# main.net
KiCad netlist of a schematic drawn in Altium Designer
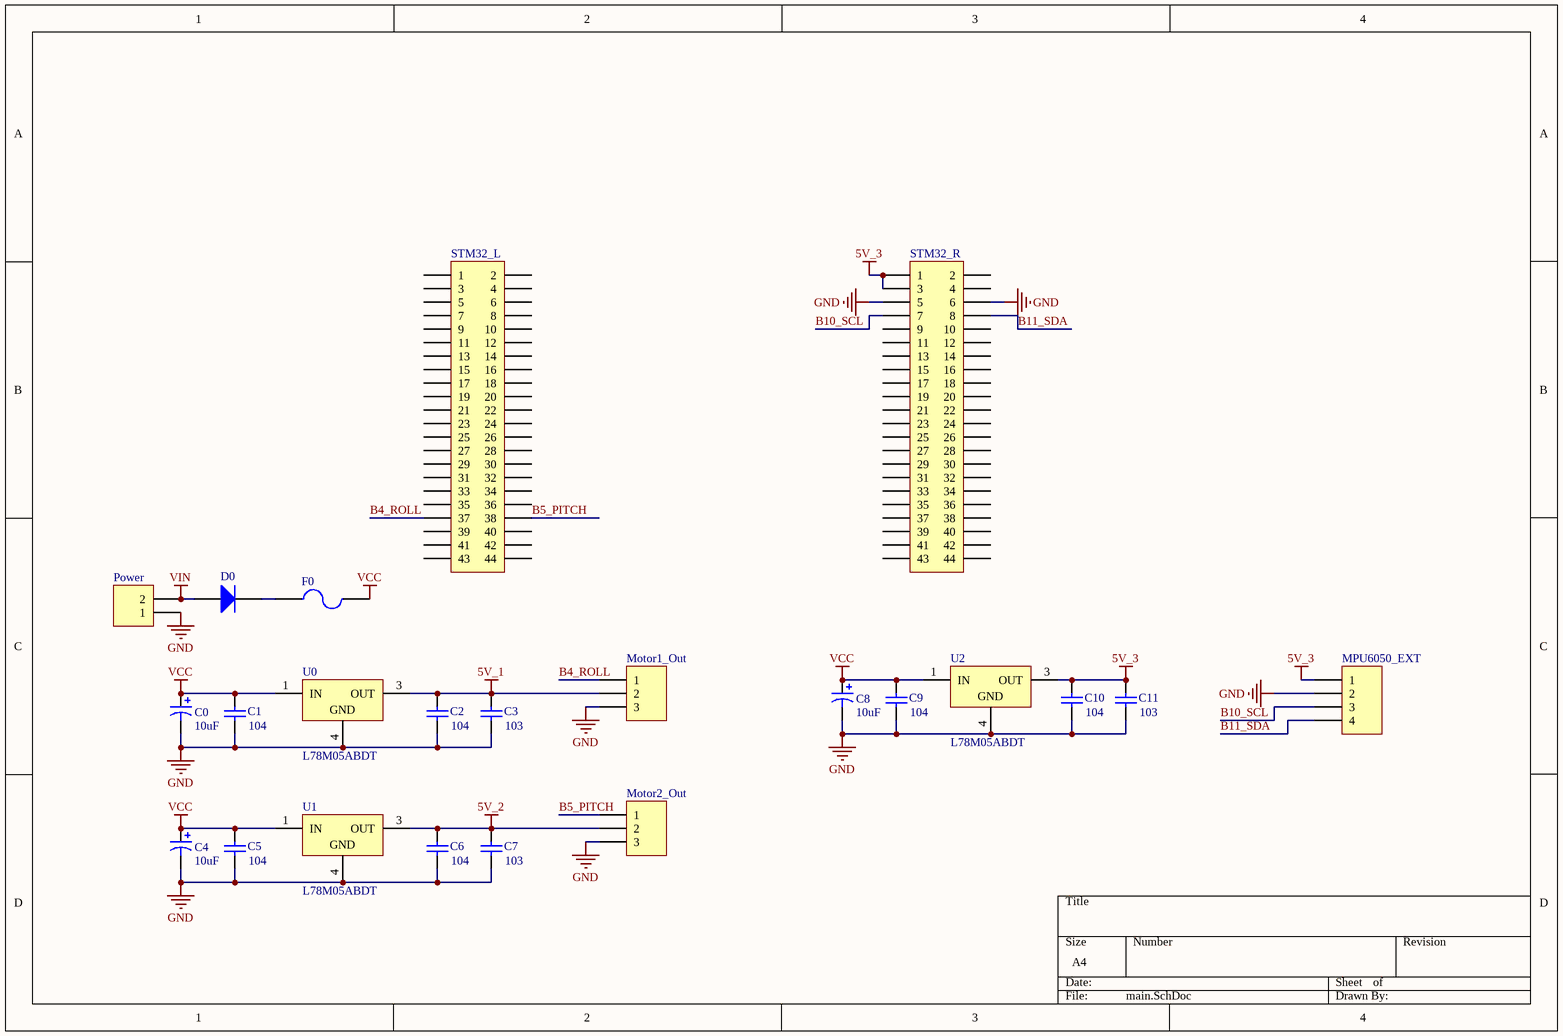
[diagram p0: main.SchDoc]

(export (version "E")
  (design (tool "Eeschema 10.0.6"))
  (components
    (comp (ref "C0")
      (value "10uF")
      (footprint "元件库:1206A")
      (description "Polarized Capacitor (Radial)")
      (fields (field (name "Comment") "Cap Pol1") (field (name "PUBLISHER") "Altium Limited"))
      (libsource (lib "Miscellaneous Devices") (part "Cap Pol1"))
    )
    (comp (ref "C1")
      (value "104")
      (footprint "STM32waiweilingjian:0805")
      (description "Capacitor (Semiconductor SIM Model)")
      (fields (field (name "Comment") "Cap Semi") (field (name "PUBLISHER") "Altium Limited"))
      (libsource (lib "Miscellaneous Devices") (part "Cap Semi"))
    )
    (comp (ref "C2")
      (value "104")
      (footprint "STM32waiweilingjian:0805")
      (description "Capacitor (Semiconductor SIM Model)")
      (fields (field (name "Comment") "Cap Semi") (field (name "PUBLISHER") "Altium Limited"))
      (libsource (lib "Miscellaneous Devices") (part "Cap Semi"))
    )
    (comp (ref "C3")
      (value "103")
      (footprint "STM32waiweilingjian:0805")
      (description "Capacitor (Semiconductor SIM Model)")
      (fields (field (name "Comment") "Cap Semi") (field (name "PUBLISHER") "Altium Limited"))
      (libsource (lib "Miscellaneous Devices") (part "Cap Semi"))
    )
    (comp (ref "C4")
      (value "10uF")
      (footprint "元件库:1206A")
      (description "Polarized Capacitor (Radial)")
      (fields (field (name "Comment") "Cap Pol1") (field (name "PUBLISHER") "Altium Limited"))
      (libsource (lib "Miscellaneous Devices") (part "Cap Pol1"))
    )
    (comp (ref "C5")
      (value "104")
      (footprint "STM32waiweilingjian:0805")
      (description "Capacitor (Semiconductor SIM Model)")
      (fields (field (name "Comment") "Cap Semi") (field (name "PUBLISHER") "Altium Limited"))
      (libsource (lib "Miscellaneous Devices") (part "Cap Semi"))
    )
    (comp (ref "C6")
      (value "104")
      (footprint "STM32waiweilingjian:0805")
      (description "Capacitor (Semiconductor SIM Model)")
      (fields (field (name "Comment") "Cap Semi") (field (name "PUBLISHER") "Altium Limited"))
      (libsource (lib "Miscellaneous Devices") (part "Cap Semi"))
    )
    (comp (ref "C7")
      (value "103")
      (footprint "STM32waiweilingjian:0805")
      (description "Capacitor (Semiconductor SIM Model)")
      (fields (field (name "Comment") "Cap Semi") (field (name "PUBLISHER") "Altium Limited"))
      (libsource (lib "Miscellaneous Devices") (part "Cap Semi"))
    )
    (comp (ref "C8")
      (value "10uF")
      (footprint "元件库:1206A")
      (description "Polarized Capacitor (Radial)")
      (fields (field (name "Comment") "Cap Pol1") (field (name "PUBLISHER") "Altium Limited"))
      (libsource (lib "Miscellaneous Devices") (part "Cap Pol1"))
    )
    (comp (ref "C9")
      (value "104")
      (footprint "STM32waiweilingjian:0805")
      (description "Capacitor (Semiconductor SIM Model)")
      (fields (field (name "Comment") "Cap Semi") (field (name "PUBLISHER") "Altium Limited"))
      (libsource (lib "Miscellaneous Devices") (part "Cap Semi"))
    )
    (comp (ref "C10")
      (value "104")
      (footprint "STM32waiweilingjian:0805")
      (description "Capacitor (Semiconductor SIM Model)")
      (fields (field (name "Comment") "Cap Semi") (field (name "PUBLISHER") "Altium Limited"))
      (libsource (lib "Miscellaneous Devices") (part "Cap Semi"))
    )
    (comp (ref "C11")
      (value "103")
      (footprint "STM32waiweilingjian:0805")
      (description "Capacitor (Semiconductor SIM Model)")
      (fields (field (name "Comment") "Cap Semi") (field (name "PUBLISHER") "Altium Limited"))
      (libsource (lib "Miscellaneous Devices") (part "Cap Semi"))
    )
    (comp (ref "D0")
      (value "Diode")
      (footprint "fszhang:DIODE-1206")
      (description "Default Diode")
      (fields (field (name "PUBLISHER") "Altium Limited"))
      (libsource (lib "Miscellaneous Devices") (part "Diode"))
    )
    (comp (ref "F0")
      (value "Fuse 2")
      (footprint "Miscellaneous Devices:1812")
      (description "Fuse")
      (fields (field (name "PUBLISHER") "Altium Limited"))
      (libsource (lib "Miscellaneous Devices") (part "Fuse 2"))
    )
    (comp (ref "Motor1_Out")
      (value "Header 3")
      (footprint "HDR1X3")
      (description "Header, 3-Pin")
      (fields (field (name "PUBLISHER") "Altium Limited"))
      (libsource (lib "Miscellaneous Connectors") (part "Header 3"))
    )
    (comp (ref "Motor2_Out")
      (value "Header 3")
      (footprint "HDR1X3")
      (description "Header, 3-Pin")
      (fields (field (name "PUBLISHER") "Altium Limited"))
      (libsource (lib "Miscellaneous Connectors") (part "Header 3"))
    )
    (comp (ref "MPU6050_EXT")
      (value "Header 4")
      (footprint "HDR1X4")
      (description "Header, 4-Pin")
      (fields (field (name "PUBLISHER") "Altium Limited"))
      (libsource (lib "Miscellaneous Connectors") (part "Header 4"))
    )
    (comp (ref "Power")
      (value "Header 2")
      (footprint "HDR1X2")
      (description "Header, 2-Pin")
      (fields (field (name "PUBLISHER") "Altium Limited"))
      (libsource (lib "Miscellaneous Connectors") (part "Header 2"))
    )
    (comp (ref "STM32_L")
      (value "Header 22X2")
      (footprint "HDR2X22")
      (description "Header, 22-Pin, Dual row")
      (fields (field (name "PUBLISHER") "Altium Limited"))
      (libsource (lib "Miscellaneous Connectors") (part "Header 22X2"))
    )
    (comp (ref "STM32_R")
      (value "Header 22X2")
      (footprint "HDR2X22")
      (description "Header, 22-Pin, Dual row")
      (fields (field (name "PUBLISHER") "Altium Limited"))
      (libsource (lib "Miscellaneous Connectors") (part "Header 22X2"))
    )
    (comp (ref "U0")
      (value "L78M05ABDT")
      (footprint "TO-252")
      (description "Precision 500mA Regulator")
      (fields (field (name "PUBLISHER") "Altium Limited"))
      (libsource (lib "ST Power Mgt Voltage Regulator") (part "L78M05ABDT"))
    )
    (comp (ref "U1")
      (value "L78M05ABDT")
      (footprint "TO-252")
      (description "Precision 500mA Regulator")
      (fields (field (name "PUBLISHER") "Altium Limited"))
      (libsource (lib "ST Power Mgt Voltage Regulator") (part "L78M05ABDT"))
    )
    (comp (ref "U2")
      (value "L78M05ABDT")
      (footprint "TO-252")
      (description "Precision 500mA Regulator")
      (fields (field (name "PUBLISHER") "Altium Limited"))
      (libsource (lib "ST Power Mgt Voltage Regulator") (part "L78M05ABDT"))
    )
  )
  (nets
    (net (code "1") (name "/B4_ROLL") (class "Default")
      (node (ref "Motor1_Out") (pin "1") (pinfunction "1_1") (pintype "passive"))
      (node (ref "STM32_L") (pin "37") (pinfunction "37_37") (pintype "passive"))
    )
    (net (code "2") (name "/B5_PITCH") (class "Default")
      (node (ref "Motor2_Out") (pin "1") (pinfunction "1_1") (pintype "passive"))
      (node (ref "STM32_L") (pin "38") (pinfunction "38_38") (pintype "passive"))
    )
    (net (code "3") (name "/B10_SCL") (class "Default")
      (node (ref "MPU6050_EXT") (pin "3") (pinfunction "3_3") (pintype "passive"))
      (node (ref "STM32_R") (pin "7") (pinfunction "7_7") (pintype "passive"))
    )
    (net (code "4") (name "/B11_SDA") (class "Default")
      (node (ref "MPU6050_EXT") (pin "4") (pinfunction "4_4") (pintype "passive"))
      (node (ref "STM32_R") (pin "8") (pinfunction "8_8") (pintype "passive"))
    )
    (net (code "5") (name "5V_1") (class "Default")
      (node (ref "C2") (pin "2") (pinfunction "2_2") (pintype "passive"))
      (node (ref "C3") (pin "2") (pinfunction "2_2") (pintype "passive"))
      (node (ref "Motor1_Out") (pin "2") (pinfunction "2_2") (pintype "passive"))
      (node (ref "U0") (pin "3") (pinfunction "OUT_3") (pintype "power_in"))
    )
    (net (code "6") (name "5V_2") (class "Default")
      (node (ref "C6") (pin "2") (pinfunction "2_2") (pintype "passive"))
      (node (ref "C7") (pin "2") (pinfunction "2_2") (pintype "passive"))
      (node (ref "Motor2_Out") (pin "2") (pinfunction "2_2") (pintype "passive"))
      (node (ref "U1") (pin "3") (pinfunction "OUT_3") (pintype "power_in"))
    )
    (net (code "7") (name "5V_3") (class "Default")
      (node (ref "C10") (pin "2") (pinfunction "2_2") (pintype "passive"))
      (node (ref "C11") (pin "2") (pinfunction "2_2") (pintype "passive"))
      (node (ref "MPU6050_EXT") (pin "1") (pinfunction "1_1") (pintype "passive"))
      (node (ref "STM32_R") (pin "1") (pinfunction "1_1") (pintype "passive"))
      (node (ref "STM32_R") (pin "3") (pinfunction "3_3") (pintype "passive"))
      (node (ref "U2") (pin "3") (pinfunction "OUT_3") (pintype "power_in"))
    )
    (net (code "8") (name "GND") (class "Default")
      (node (ref "C0") (pin "2") (pinfunction "2_2") (pintype "passive"))
      (node (ref "C1") (pin "1") (pinfunction "1_1") (pintype "passive"))
      (node (ref "C10") (pin "1") (pinfunction "1_1") (pintype "passive"))
      (node (ref "C11") (pin "1") (pinfunction "1_1") (pintype "passive"))
      (node (ref "C2") (pin "1") (pinfunction "1_1") (pintype "passive"))
      (node (ref "C3") (pin "1") (pinfunction "1_1") (pintype "passive"))
      (node (ref "C4") (pin "2") (pinfunction "2_2") (pintype "passive"))
      (node (ref "C5") (pin "1") (pinfunction "1_1") (pintype "passive"))
      (node (ref "C6") (pin "1") (pinfunction "1_1") (pintype "passive"))
      (node (ref "C7") (pin "1") (pinfunction "1_1") (pintype "passive"))
      (node (ref "C8") (pin "2") (pinfunction "2_2") (pintype "passive"))
      (node (ref "C9") (pin "1") (pinfunction "1_1") (pintype "passive"))
      (node (ref "MPU6050_EXT") (pin "2") (pinfunction "2_2") (pintype "passive"))
      (node (ref "Motor1_Out") (pin "3") (pinfunction "3_3") (pintype "passive"))
      (node (ref "Motor2_Out") (pin "3") (pinfunction "3_3") (pintype "passive"))
      (node (ref "Power") (pin "1") (pinfunction "1_1") (pintype "passive"))
      (node (ref "STM32_R") (pin "5") (pinfunction "5_5") (pintype "passive"))
      (node (ref "STM32_R") (pin "6") (pinfunction "6_6") (pintype "passive"))
      (node (ref "U0") (pin "4") (pinfunction "GND_4") (pintype "power_in"))
      (node (ref "U1") (pin "4") (pinfunction "GND_4") (pintype "power_in"))
      (node (ref "U2") (pin "4") (pinfunction "GND_4") (pintype "power_in"))
    )
    (net (code "9") (name "Net-(D0-K)") (class "Default")
      (node (ref "D0") (pin "2") (pinfunction "K_2") (pintype "passive"))
      (node (ref "F0") (pin "1") (pinfunction "1_1") (pintype "passive"))
    )
    (net (code "10") (name "VCC") (class "Default")
      (node (ref "C0") (pin "1") (pinfunction "1_1") (pintype "passive"))
      (node (ref "C1") (pin "2") (pinfunction "2_2") (pintype "passive"))
      (node (ref "C4") (pin "1") (pinfunction "1_1") (pintype "passive"))
      (node (ref "C5") (pin "2") (pinfunction "2_2") (pintype "passive"))
      (node (ref "C8") (pin "1") (pinfunction "1_1") (pintype "passive"))
      (node (ref "C9") (pin "2") (pinfunction "2_2") (pintype "passive"))
      (node (ref "F0") (pin "2") (pinfunction "2_2") (pintype "passive"))
      (node (ref "U0") (pin "1") (pinfunction "IN_1") (pintype "power_in"))
      (node (ref "U1") (pin "1") (pinfunction "IN_1") (pintype "power_in"))
      (node (ref "U2") (pin "1") (pinfunction "IN_1") (pintype "power_in"))
    )
    (net (code "11") (name "VIN") (class "Default")
      (node (ref "D0") (pin "1") (pinfunction "A_1") (pintype "passive"))
      (node (ref "Power") (pin "2") (pinfunction "2_2") (pintype "passive"))
    )
    (net (code "12") (name "unconnected-(STM32_L-Pad1)") (class "Default")
      (node (ref "STM32_L") (pin "1") (pinfunction "1_1") (pintype "passive"))
    )
    (net (code "13") (name "unconnected-(STM32_L-Pad2)") (class "Default")
      (node (ref "STM32_L") (pin "2") (pinfunction "2_2") (pintype "passive"))
    )
    (net (code "14") (name "unconnected-(STM32_L-Pad3)") (class "Default")
      (node (ref "STM32_L") (pin "3") (pinfunction "3_3") (pintype "passive"))
    )
    (net (code "15") (name "unconnected-(STM32_L-Pad4)") (class "Default")
      (node (ref "STM32_L") (pin "4") (pinfunction "4_4") (pintype "passive"))
    )
    (net (code "16") (name "unconnected-(STM32_L-Pad5)") (class "Default")
      (node (ref "STM32_L") (pin "5") (pinfunction "5_5") (pintype "passive"))
    )
    (net (code "17") (name "unconnected-(STM32_L-Pad6)") (class "Default")
      (node (ref "STM32_L") (pin "6") (pinfunction "6_6") (pintype "passive"))
    )
    (net (code "18") (name "unconnected-(STM32_L-Pad7)") (class "Default")
      (node (ref "STM32_L") (pin "7") (pinfunction "7_7") (pintype "passive"))
    )
    (net (code "19") (name "unconnected-(STM32_L-Pad8)") (class "Default")
      (node (ref "STM32_L") (pin "8") (pinfunction "8_8") (pintype "passive"))
    )
    (net (code "20") (name "unconnected-(STM32_L-Pad9)") (class "Default")
      (node (ref "STM32_L") (pin "9") (pinfunction "9_9") (pintype "passive"))
    )
    (net (code "21") (name "unconnected-(STM32_L-Pad10)") (class "Default")
      (node (ref "STM32_L") (pin "10") (pinfunction "10_10") (pintype "passive"))
    )
    (net (code "22") (name "unconnected-(STM32_L-Pad11)") (class "Default")
      (node (ref "STM32_L") (pin "11") (pinfunction "11_11") (pintype "passive"))
    )
    (net (code "23") (name "unconnected-(STM32_L-Pad12)") (class "Default")
      (node (ref "STM32_L") (pin "12") (pinfunction "12_12") (pintype "passive"))
    )
    (net (code "24") (name "unconnected-(STM32_L-Pad13)") (class "Default")
      (node (ref "STM32_L") (pin "13") (pinfunction "13_13") (pintype "passive"))
    )
    (net (code "25") (name "unconnected-(STM32_L-Pad14)") (class "Default")
      (node (ref "STM32_L") (pin "14") (pinfunction "14_14") (pintype "passive"))
    )
    (net (code "26") (name "unconnected-(STM32_L-Pad15)") (class "Default")
      (node (ref "STM32_L") (pin "15") (pinfunction "15_15") (pintype "passive"))
    )
    (net (code "27") (name "unconnected-(STM32_L-Pad16)") (class "Default")
      (node (ref "STM32_L") (pin "16") (pinfunction "16_16") (pintype "passive"))
    )
    (net (code "28") (name "unconnected-(STM32_L-Pad17)") (class "Default")
      (node (ref "STM32_L") (pin "17") (pinfunction "17_17") (pintype "passive"))
    )
    (net (code "29") (name "unconnected-(STM32_L-Pad18)") (class "Default")
      (node (ref "STM32_L") (pin "18") (pinfunction "18_18") (pintype "passive"))
    )
    (net (code "30") (name "unconnected-(STM32_L-Pad19)") (class "Default")
      (node (ref "STM32_L") (pin "19") (pinfunction "19_19") (pintype "passive"))
    )
    (net (code "31") (name "unconnected-(STM32_L-Pad20)") (class "Default")
      (node (ref "STM32_L") (pin "20") (pinfunction "20_20") (pintype "passive"))
    )
    (net (code "32") (name "unconnected-(STM32_L-Pad21)") (class "Default")
      (node (ref "STM32_L") (pin "21") (pinfunction "21_21") (pintype "passive"))
    )
    (net (code "33") (name "unconnected-(STM32_L-Pad22)") (class "Default")
      (node (ref "STM32_L") (pin "22") (pinfunction "22_22") (pintype "passive"))
    )
    (net (code "34") (name "unconnected-(STM32_L-Pad23)") (class "Default")
      (node (ref "STM32_L") (pin "23") (pinfunction "23_23") (pintype "passive"))
    )
    (net (code "35") (name "unconnected-(STM32_L-Pad24)") (class "Default")
      (node (ref "STM32_L") (pin "24") (pinfunction "24_24") (pintype "passive"))
    )
    (net (code "36") (name "unconnected-(STM32_L-Pad25)") (class "Default")
      (node (ref "STM32_L") (pin "25") (pinfunction "25_25") (pintype "passive"))
    )
    (net (code "37") (name "unconnected-(STM32_L-Pad26)") (class "Default")
      (node (ref "STM32_L") (pin "26") (pinfunction "26_26") (pintype "passive"))
    )
    (net (code "38") (name "unconnected-(STM32_L-Pad27)") (class "Default")
      (node (ref "STM32_L") (pin "27") (pinfunction "27_27") (pintype "passive"))
    )
    (net (code "39") (name "unconnected-(STM32_L-Pad28)") (class "Default")
      (node (ref "STM32_L") (pin "28") (pinfunction "28_28") (pintype "passive"))
    )
    (net (code "40") (name "unconnected-(STM32_L-Pad29)") (class "Default")
      (node (ref "STM32_L") (pin "29") (pinfunction "29_29") (pintype "passive"))
    )
    (net (code "41") (name "unconnected-(STM32_L-Pad30)") (class "Default")
      (node (ref "STM32_L") (pin "30") (pinfunction "30_30") (pintype "passive"))
    )
    (net (code "42") (name "unconnected-(STM32_L-Pad31)") (class "Default")
      (node (ref "STM32_L") (pin "31") (pinfunction "31_31") (pintype "passive"))
    )
    (net (code "43") (name "unconnected-(STM32_L-Pad32)") (class "Default")
      (node (ref "STM32_L") (pin "32") (pinfunction "32_32") (pintype "passive"))
    )
    (net (code "44") (name "unconnected-(STM32_L-Pad33)") (class "Default")
      (node (ref "STM32_L") (pin "33") (pinfunction "33_33") (pintype "passive"))
    )
    (net (code "45") (name "unconnected-(STM32_L-Pad34)") (class "Default")
      (node (ref "STM32_L") (pin "34") (pinfunction "34_34") (pintype "passive"))
    )
    (net (code "46") (name "unconnected-(STM32_L-Pad35)") (class "Default")
      (node (ref "STM32_L") (pin "35") (pinfunction "35_35") (pintype "passive"))
    )
    (net (code "47") (name "unconnected-(STM32_L-Pad36)") (class "Default")
      (node (ref "STM32_L") (pin "36") (pinfunction "36_36") (pintype "passive"))
    )
    (net (code "48") (name "unconnected-(STM32_L-Pad39)") (class "Default")
      (node (ref "STM32_L") (pin "39") (pinfunction "39_39") (pintype "passive"))
    )
    (net (code "49") (name "unconnected-(STM32_L-Pad40)") (class "Default")
      (node (ref "STM32_L") (pin "40") (pinfunction "40_40") (pintype "passive"))
    )
    (net (code "50") (name "unconnected-(STM32_L-Pad41)") (class "Default")
      (node (ref "STM32_L") (pin "41") (pinfunction "41_41") (pintype "passive"))
    )
    (net (code "51") (name "unconnected-(STM32_L-Pad42)") (class "Default")
      (node (ref "STM32_L") (pin "42") (pinfunction "42_42") (pintype "passive"))
    )
    (net (code "52") (name "unconnected-(STM32_L-Pad43)") (class "Default")
      (node (ref "STM32_L") (pin "43") (pinfunction "43_43") (pintype "passive"))
    )
    (net (code "53") (name "unconnected-(STM32_L-Pad44)") (class "Default")
      (node (ref "STM32_L") (pin "44") (pinfunction "44_44") (pintype "passive"))
    )
    (net (code "54") (name "unconnected-(STM32_R-Pad2)") (class "Default")
      (node (ref "STM32_R") (pin "2") (pinfunction "2_2") (pintype "passive"))
    )
    (net (code "55") (name "unconnected-(STM32_R-Pad4)") (class "Default")
      (node (ref "STM32_R") (pin "4") (pinfunction "4_4") (pintype "passive"))
    )
    (net (code "56") (name "unconnected-(STM32_R-Pad9)") (class "Default")
      (node (ref "STM32_R") (pin "9") (pinfunction "9_9") (pintype "passive"))
    )
    (net (code "57") (name "unconnected-(STM32_R-Pad10)") (class "Default")
      (node (ref "STM32_R") (pin "10") (pinfunction "10_10") (pintype "passive"))
    )
    (net (code "58") (name "unconnected-(STM32_R-Pad11)") (class "Default")
      (node (ref "STM32_R") (pin "11") (pinfunction "11_11") (pintype "passive"))
    )
    (net (code "59") (name "unconnected-(STM32_R-Pad12)") (class "Default")
      (node (ref "STM32_R") (pin "12") (pinfunction "12_12") (pintype "passive"))
    )
    (net (code "60") (name "unconnected-(STM32_R-Pad13)") (class "Default")
      (node (ref "STM32_R") (pin "13") (pinfunction "13_13") (pintype "passive"))
    )
    (net (code "61") (name "unconnected-(STM32_R-Pad14)") (class "Default")
      (node (ref "STM32_R") (pin "14") (pinfunction "14_14") (pintype "passive"))
    )
    (net (code "62") (name "unconnected-(STM32_R-Pad15)") (class "Default")
      (node (ref "STM32_R") (pin "15") (pinfunction "15_15") (pintype "passive"))
    )
    (net (code "63") (name "unconnected-(STM32_R-Pad16)") (class "Default")
      (node (ref "STM32_R") (pin "16") (pinfunction "16_16") (pintype "passive"))
    )
    (net (code "64") (name "unconnected-(STM32_R-Pad17)") (class "Default")
      (node (ref "STM32_R") (pin "17") (pinfunction "17_17") (pintype "passive"))
    )
    (net (code "65") (name "unconnected-(STM32_R-Pad18)") (class "Default")
      (node (ref "STM32_R") (pin "18") (pinfunction "18_18") (pintype "passive"))
    )
    (net (code "66") (name "unconnected-(STM32_R-Pad19)") (class "Default")
      (node (ref "STM32_R") (pin "19") (pinfunction "19_19") (pintype "passive"))
    )
    (net (code "67") (name "unconnected-(STM32_R-Pad20)") (class "Default")
      (node (ref "STM32_R") (pin "20") (pinfunction "20_20") (pintype "passive"))
    )
    (net (code "68") (name "unconnected-(STM32_R-Pad21)") (class "Default")
      (node (ref "STM32_R") (pin "21") (pinfunction "21_21") (pintype "passive"))
    )
    (net (code "69") (name "unconnected-(STM32_R-Pad22)") (class "Default")
      (node (ref "STM32_R") (pin "22") (pinfunction "22_22") (pintype "passive"))
    )
    (net (code "70") (name "unconnected-(STM32_R-Pad23)") (class "Default")
      (node (ref "STM32_R") (pin "23") (pinfunction "23_23") (pintype "passive"))
    )
    (net (code "71") (name "unconnected-(STM32_R-Pad24)") (class "Default")
      (node (ref "STM32_R") (pin "24") (pinfunction "24_24") (pintype "passive"))
    )
    (net (code "72") (name "unconnected-(STM32_R-Pad25)") (class "Default")
      (node (ref "STM32_R") (pin "25") (pinfunction "25_25") (pintype "passive"))
    )
    (net (code "73") (name "unconnected-(STM32_R-Pad26)") (class "Default")
      (node (ref "STM32_R") (pin "26") (pinfunction "26_26") (pintype "passive"))
    )
    (net (code "74") (name "unconnected-(STM32_R-Pad27)") (class "Default")
      (node (ref "STM32_R") (pin "27") (pinfunction "27_27") (pintype "passive"))
    )
    (net (code "75") (name "unconnected-(STM32_R-Pad28)") (class "Default")
      (node (ref "STM32_R") (pin "28") (pinfunction "28_28") (pintype "passive"))
    )
    (net (code "76") (name "unconnected-(STM32_R-Pad29)") (class "Default")
      (node (ref "STM32_R") (pin "29") (pinfunction "29_29") (pintype "passive"))
    )
    (net (code "77") (name "unconnected-(STM32_R-Pad30)") (class "Default")
      (node (ref "STM32_R") (pin "30") (pinfunction "30_30") (pintype "passive"))
    )
    (net (code "78") (name "unconnected-(STM32_R-Pad31)") (class "Default")
      (node (ref "STM32_R") (pin "31") (pinfunction "31_31") (pintype "passive"))
    )
    (net (code "79") (name "unconnected-(STM32_R-Pad32)") (class "Default")
      (node (ref "STM32_R") (pin "32") (pinfunction "32_32") (pintype "passive"))
    )
    (net (code "80") (name "unconnected-(STM32_R-Pad33)") (class "Default")
      (node (ref "STM32_R") (pin "33") (pinfunction "33_33") (pintype "passive"))
    )
    (net (code "81") (name "unconnected-(STM32_R-Pad34)") (class "Default")
      (node (ref "STM32_R") (pin "34") (pinfunction "34_34") (pintype "passive"))
    )
    (net (code "82") (name "unconnected-(STM32_R-Pad35)") (class "Default")
      (node (ref "STM32_R") (pin "35") (pinfunction "35_35") (pintype "passive"))
    )
    (net (code "83") (name "unconnected-(STM32_R-Pad36)") (class "Default")
      (node (ref "STM32_R") (pin "36") (pinfunction "36_36") (pintype "passive"))
    )
    (net (code "84") (name "unconnected-(STM32_R-Pad37)") (class "Default")
      (node (ref "STM32_R") (pin "37") (pinfunction "37_37") (pintype "passive"))
    )
    (net (code "85") (name "unconnected-(STM32_R-Pad38)") (class "Default")
      (node (ref "STM32_R") (pin "38") (pinfunction "38_38") (pintype "passive"))
    )
    (net (code "86") (name "unconnected-(STM32_R-Pad39)") (class "Default")
      (node (ref "STM32_R") (pin "39") (pinfunction "39_39") (pintype "passive"))
    )
    (net (code "87") (name "unconnected-(STM32_R-Pad40)") (class "Default")
      (node (ref "STM32_R") (pin "40") (pinfunction "40_40") (pintype "passive"))
    )
    (net (code "88") (name "unconnected-(STM32_R-Pad41)") (class "Default")
      (node (ref "STM32_R") (pin "41") (pinfunction "41_41") (pintype "passive"))
    )
    (net (code "89") (name "unconnected-(STM32_R-Pad42)") (class "Default")
      (node (ref "STM32_R") (pin "42") (pinfunction "42_42") (pintype "passive"))
    )
    (net (code "90") (name "unconnected-(STM32_R-Pad43)") (class "Default")
      (node (ref "STM32_R") (pin "43") (pinfunction "43_43") (pintype "passive"))
    )
    (net (code "91") (name "unconnected-(STM32_R-Pad44)") (class "Default")
      (node (ref "STM32_R") (pin "44") (pinfunction "44_44") (pintype "passive"))
    )
  )
)
